# wirelessrgbled.net
KiCad netlist of a schematic drawn in EAGLE
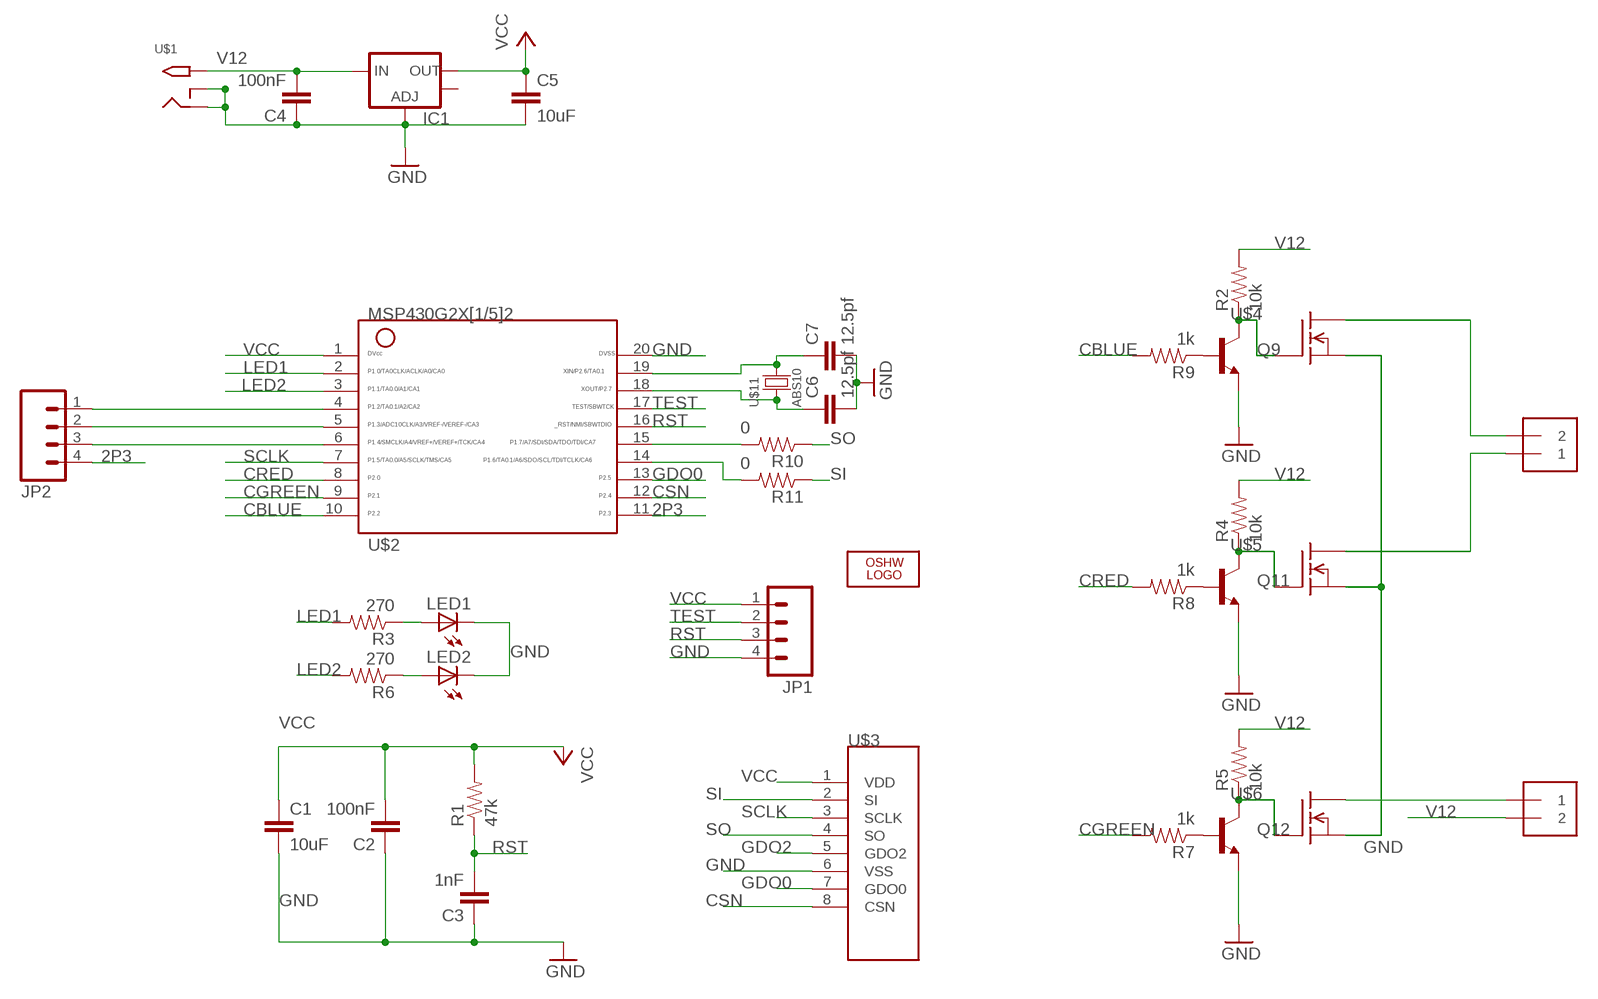
[diagram p0: schematic, sheet 1]

(export (version "E")
  (design (tool "Eeschema 10.0.6"))
  (components
    (comp (ref "C1")
      (value "10uF")
      (footprint "eagle-import:0805")
      (libsource (lib "eagle-import") (part "CAP0805"))
    )
    (comp (ref "C2")
      (value "100nF")
      (footprint "eagle-import:0805")
      (libsource (lib "eagle-import") (part "CAP0805"))
    )
    (comp (ref "C3")
      (value "1nF")
      (footprint "eagle-import:0805")
      (libsource (lib "eagle-import") (part "CAP0805"))
    )
    (comp (ref "C4")
      (value "100nF")
      (footprint "eagle-import:0805")
      (libsource (lib "eagle-import") (part "CAP0805"))
    )
    (comp (ref "C5")
      (value "10uF")
      (footprint "eagle-import:0805")
      (libsource (lib "eagle-import") (part "CAP0805"))
    )
    (comp (ref "C6")
      (value "12.5pf")
      (footprint "eagle-import:0805")
      (libsource (lib "eagle-import") (part "CAP0805"))
    )
    (comp (ref "C7")
      (value "12.5pf")
      (footprint "eagle-import:0805")
      (libsource (lib "eagle-import") (part "CAP0805"))
    )
    (comp (ref "IC1")
      (value "V_REG_LM1117SOT223")
      (footprint "eagle-import:SOT223")
      (libsource (lib "eagle-import") (part "V_REG_LM1117SOT223"))
    )
    (comp (ref "J1")
      (value "1X2-3.5MM")
      (footprint "eagle-import:1X2-3.5MM")
      (libsource (lib "eagle-import") (part "1X2-3.5MM"))
    )
    (comp (ref "J2")
      (value "1X2-3.5MM")
      (footprint "eagle-import:1X2-3.5MM")
      (libsource (lib "eagle-import") (part "1X2-3.5MM"))
    )
    (comp (ref "JP1")
      (value "M04PTH")
      (footprint "eagle-import:1X04")
      (libsource (lib "eagle-import") (part "M04PTH"))
    )
    (comp (ref "JP2")
      (value "M04PTH")
      (footprint "eagle-import:1X04")
      (libsource (lib "eagle-import") (part "M04PTH"))
    )
    (comp (ref "LED1")
      (value "LEDCHIPLED_0805")
      (footprint "eagle-import:CHIPLED_0805")
      (libsource (lib "eagle-import") (part "LEDCHIPLED_0805"))
    )
    (comp (ref "LED2")
      (value "LEDCHIPLED_0805")
      (footprint "eagle-import:CHIPLED_0805")
      (libsource (lib "eagle-import") (part "LEDCHIPLED_0805"))
    )
    (comp (ref "LOGO1")
      (value "OSHW_LOGO_10MILX0200-NT")
      (footprint "eagle-import:OSHW_10X200_NOTEXT")
      (libsource (lib "eagle-import") (part "OSHW_LOGO_10MILX0200-NT"))
    )
    (comp (ref "Q9")
      (value "TRANSISTOR_NPNSOT23")
      (footprint "eagle-import:SOT23")
      (libsource (lib "eagle-import") (part "TRANSISTOR_NPNSOT23"))
    )
    (comp (ref "Q11")
      (value "TRANSISTOR_NPNSOT23")
      (footprint "eagle-import:SOT23")
      (libsource (lib "eagle-import") (part "TRANSISTOR_NPNSOT23"))
    )
    (comp (ref "Q12")
      (value "TRANSISTOR_NPNSOT23")
      (footprint "eagle-import:SOT23")
      (libsource (lib "eagle-import") (part "TRANSISTOR_NPNSOT23"))
    )
    (comp (ref "R1")
      (value "47k")
      (footprint "eagle-import:0805")
      (libsource (lib "eagle-import") (part "RESISTOR0805-RES"))
    )
    (comp (ref "R2")
      (value "10k")
      (footprint "eagle-import:0805")
      (libsource (lib "eagle-import") (part "RESISTOR0805-RES"))
    )
    (comp (ref "R3")
      (value "270")
      (footprint "eagle-import:0805")
      (libsource (lib "eagle-import") (part "RESISTOR0805-RES"))
    )
    (comp (ref "R4")
      (value "10k")
      (footprint "eagle-import:0805")
      (libsource (lib "eagle-import") (part "RESISTOR0805-RES"))
    )
    (comp (ref "R5")
      (value "10k")
      (footprint "eagle-import:0805")
      (libsource (lib "eagle-import") (part "RESISTOR0805-RES"))
    )
    (comp (ref "R6")
      (value "270")
      (footprint "eagle-import:0805")
      (libsource (lib "eagle-import") (part "RESISTOR0805-RES"))
    )
    (comp (ref "R7")
      (value "1k")
      (footprint "eagle-import:0805")
      (libsource (lib "eagle-import") (part "RESISTOR0805-RES"))
    )
    (comp (ref "R8")
      (value "1k")
      (footprint "eagle-import:0805")
      (libsource (lib "eagle-import") (part "RESISTOR0805-RES"))
    )
    (comp (ref "R9")
      (value "1k")
      (footprint "eagle-import:0805")
      (libsource (lib "eagle-import") (part "RESISTOR0805-RES"))
    )
    (comp (ref "R10")
      (value "0")
      (footprint "eagle-import:0805")
      (libsource (lib "eagle-import") (part "RESISTOR0805-RES"))
    )
    (comp (ref "R11")
      (value "0")
      (footprint "eagle-import:0805")
      (libsource (lib "eagle-import") (part "RESISTOR0805-RES"))
    )
    (comp (ref "U$1")
      (value "2.1MMJACKTHM")
      (footprint "eagle-import:PJ-102A")
      (libsource (lib "eagle-import") (part "2.1MMJACKTHM"))
    )
    (comp (ref "U$2")
      (value "G2X[1/5]2---PW20")
      (footprint "eagle-import:PW20")
      (libsource (lib "eagle-import") (part "G2X[1/5]2---PW20"))
    )
    (comp (ref "U$3")
      (value "CC2500-MODULE")
      (footprint "eagle-import:CC2500-MODULE")
      (libsource (lib "eagle-import") (part "CC2500-MODULE"))
    )
    (comp (ref "U$4")
      (value "BUK92150")
      (footprint "eagle-import:TO252")
      (libsource (lib "eagle-import") (part "BUK92150"))
    )
    (comp (ref "U$5")
      (value "BUK92150")
      (footprint "eagle-import:TO252")
      (libsource (lib "eagle-import") (part "BUK92150"))
    )
    (comp (ref "U$6")
      (value "BUK92150")
      (footprint "eagle-import:TO252")
      (libsource (lib "eagle-import") (part "BUK92150"))
    )
    (comp (ref "U$11")
      (value "ABS10")
      (footprint "eagle-import:ABS10")
      (libsource (lib "eagle-import") (part "ABS10"))
    )
  )
  (nets
    (net (code "1") (name "/2P3") (class "Default")
      (node (ref "JP2") (pin "4") (pinfunction "4_4") (pintype "passive"))
      (node (ref "U$2") (pin "11") (pinfunction "11_11") (pintype "bidirectional"))
    )
    (net (code "2") (name "/CBLUE") (class "Default")
      (node (ref "R9") (pin "2") (pinfunction "2_2") (pintype "passive"))
      (node (ref "U$2") (pin "10") (pinfunction "10_10") (pintype "bidirectional"))
    )
    (net (code "3") (name "/CGREEN") (class "Default")
      (node (ref "R7") (pin "2") (pinfunction "2_2") (pintype "passive"))
      (node (ref "U$2") (pin "9") (pinfunction "9_9") (pintype "bidirectional"))
    )
    (net (code "4") (name "/CRED") (class "Default")
      (node (ref "R8") (pin "2") (pinfunction "2_2") (pintype "passive"))
      (node (ref "U$2") (pin "8") (pinfunction "8_8") (pintype "bidirectional"))
    )
    (net (code "5") (name "/CSN") (class "Default")
      (node (ref "U$2") (pin "12") (pinfunction "12_12") (pintype "bidirectional"))
      (node (ref "U$3") (pin "8") (pinfunction "CSN_8") (pintype "bidirectional"))
    )
    (net (code "6") (name "/GDO0") (class "Default")
      (node (ref "U$2") (pin "13") (pinfunction "13_13") (pintype "bidirectional"))
      (node (ref "U$3") (pin "7") (pinfunction "GDO0_7") (pintype "bidirectional"))
    )
    (net (code "7") (name "/GDO2") (class "Default")
      (node (ref "U$3") (pin "5") (pinfunction "GDO2_5") (pintype "bidirectional"))
    )
    (net (code "8") (name "/LED1") (class "Default")
      (node (ref "R3") (pin "2") (pinfunction "2_2") (pintype "passive"))
      (node (ref "U$2") (pin "2") (pinfunction "2_2") (pintype "bidirectional"))
    )
    (net (code "9") (name "/LED2") (class "Default")
      (node (ref "R6") (pin "2") (pinfunction "2_2") (pintype "passive"))
      (node (ref "U$2") (pin "3") (pinfunction "3_3") (pintype "bidirectional"))
    )
    (net (code "10") (name "/RST") (class "Default")
      (node (ref "C3") (pin "2") (pinfunction "2_2") (pintype "passive"))
      (node (ref "JP1") (pin "3") (pinfunction "3_3") (pintype "passive"))
      (node (ref "R1") (pin "1") (pinfunction "1_1") (pintype "passive"))
      (node (ref "U$2") (pin "16") (pinfunction "16_16") (pintype "bidirectional"))
    )
    (net (code "11") (name "/SCLK") (class "Default")
      (node (ref "U$2") (pin "7") (pinfunction "7_7") (pintype "bidirectional"))
      (node (ref "U$3") (pin "3") (pinfunction "SCLK_3") (pintype "bidirectional"))
    )
    (net (code "12") (name "/SI") (class "Default")
      (node (ref "R11") (pin "1") (pinfunction "1_1") (pintype "passive"))
      (node (ref "U$3") (pin "2") (pinfunction "SI_2") (pintype "bidirectional"))
    )
    (net (code "13") (name "/SO") (class "Default")
      (node (ref "R10") (pin "1") (pinfunction "1_1") (pintype "passive"))
      (node (ref "U$3") (pin "4") (pinfunction "SO_4") (pintype "bidirectional"))
    )
    (net (code "14") (name "/TEST") (class "Default")
      (node (ref "JP1") (pin "2") (pinfunction "2_2") (pintype "passive"))
      (node (ref "U$2") (pin "17") (pinfunction "17_17") (pintype "bidirectional"))
    )
    (net (code "15") (name "/V12") (class "Default")
      (node (ref "C4") (pin "2") (pinfunction "2_2") (pintype "passive"))
      (node (ref "IC1") (pin "3") (pinfunction "IN_3") (pintype "input"))
      (node (ref "J2") (pin "2") (pinfunction "2_2") (pintype "passive"))
      (node (ref "R2") (pin "2") (pinfunction "2_2") (pintype "passive"))
      (node (ref "R4") (pin "2") (pinfunction "2_2") (pintype "passive"))
      (node (ref "R5") (pin "2") (pinfunction "2_2") (pintype "passive"))
      (node (ref "U$1") (pin "TIP") (pinfunction "TIP_TIP") (pintype "bidirectional"))
    )
    (net (code "16") (name "GND") (class "Default")
      (node (ref "C1") (pin "2") (pinfunction "2_2") (pintype "passive"))
      (node (ref "C2") (pin "1") (pinfunction "1_1") (pintype "passive"))
      (node (ref "C3") (pin "1") (pinfunction "1_1") (pintype "passive"))
      (node (ref "C4") (pin "1") (pinfunction "1_1") (pintype "passive"))
      (node (ref "C5") (pin "2") (pinfunction "2_2") (pintype "passive"))
      (node (ref "C6") (pin "2") (pinfunction "2_2") (pintype "passive"))
      (node (ref "C7") (pin "2") (pinfunction "2_2") (pintype "passive"))
      (node (ref "IC1") (pin "1") (pinfunction "ADJ_1") (pintype "input"))
      (node (ref "JP1") (pin "4") (pinfunction "4_4") (pintype "passive"))
      (node (ref "LED1") (pin "C") (pinfunction "C_C") (pintype "passive"))
      (node (ref "LED2") (pin "C") (pinfunction "C_C") (pintype "passive"))
      (node (ref "Q11") (pin "2") (pinfunction "E_2") (pintype "passive"))
      (node (ref "Q12") (pin "2") (pinfunction "E_2") (pintype "passive"))
      (node (ref "Q9") (pin "2") (pinfunction "E_2") (pintype "passive"))
      (node (ref "U$1") (pin "RING") (pinfunction "RING_RING") (pintype "bidirectional"))
      (node (ref "U$1") (pin "RING_SW") (pinfunction "RING_SW_RING_SW") (pintype "bidirectional"))
      (node (ref "U$2") (pin "20") (pinfunction "20_20") (pintype "bidirectional"))
      (node (ref "U$3") (pin "6") (pinfunction "VSS_6") (pintype "bidirectional"))
      (node (ref "U$4") (pin "3") (pinfunction "S_3") (pintype "passive"))
      (node (ref "U$5") (pin "3") (pinfunction "S_3") (pintype "passive"))
      (node (ref "U$6") (pin "3") (pinfunction "S_3") (pintype "passive"))
    )
    (net (code "17") (name "Net-(C6-Pad1)") (class "Default")
      (node (ref "C6") (pin "1") (pinfunction "1_1") (pintype "passive"))
      (node (ref "U$11") (pin "P$1") (pinfunction "P$1_P$1") (pintype "passive"))
      (node (ref "U$2") (pin "18") (pinfunction "18_18") (pintype "bidirectional"))
    )
    (net (code "18") (name "Net-(C7-Pad1)") (class "Default")
      (node (ref "C7") (pin "1") (pinfunction "1_1") (pintype "passive"))
      (node (ref "U$11") (pin "P$2") (pinfunction "P$2_P$2") (pintype "passive"))
      (node (ref "U$2") (pin "19") (pinfunction "19_19") (pintype "bidirectional"))
    )
    (net (code "19") (name "Net-(JP2-Pad1)") (class "Default")
      (node (ref "JP2") (pin "1") (pinfunction "1_1") (pintype "passive"))
      (node (ref "U$2") (pin "4") (pinfunction "4_4") (pintype "bidirectional"))
    )
    (net (code "20") (name "Net-(JP2-Pad2)") (class "Default")
      (node (ref "JP2") (pin "2") (pinfunction "2_2") (pintype "passive"))
      (node (ref "U$2") (pin "5") (pinfunction "5_5") (pintype "bidirectional"))
    )
    (net (code "21") (name "Net-(JP2-Pad3)") (class "Default")
      (node (ref "JP2") (pin "3") (pinfunction "3_3") (pintype "passive"))
      (node (ref "U$2") (pin "6") (pinfunction "6_6") (pintype "bidirectional"))
    )
    (net (code "22") (name "Net-(LED1-PadA)") (class "Default")
      (node (ref "LED1") (pin "A") (pinfunction "A_A") (pintype "passive"))
      (node (ref "R3") (pin "1") (pinfunction "1_1") (pintype "passive"))
    )
    (net (code "23") (name "Net-(LED2-PadA)") (class "Default")
      (node (ref "LED2") (pin "A") (pinfunction "A_A") (pintype "passive"))
      (node (ref "R6") (pin "1") (pinfunction "1_1") (pintype "passive"))
    )
    (net (code "24") (name "Net-(Q9-B)") (class "Default")
      (node (ref "Q9") (pin "1") (pinfunction "B_1") (pintype "passive"))
      (node (ref "R9") (pin "1") (pinfunction "1_1") (pintype "passive"))
    )
    (net (code "25") (name "Net-(Q9-C)") (class "Default")
      (node (ref "Q9") (pin "3") (pinfunction "C_3") (pintype "passive"))
      (node (ref "R2") (pin "1") (pinfunction "1_1") (pintype "passive"))
      (node (ref "U$4") (pin "1") (pinfunction "G_1") (pintype "passive"))
    )
    (net (code "26") (name "Net-(Q11-B)") (class "Default")
      (node (ref "Q11") (pin "1") (pinfunction "B_1") (pintype "passive"))
      (node (ref "R8") (pin "1") (pinfunction "1_1") (pintype "passive"))
    )
    (net (code "27") (name "Net-(Q11-C)") (class "Default")
      (node (ref "Q11") (pin "3") (pinfunction "C_3") (pintype "passive"))
      (node (ref "R4") (pin "1") (pinfunction "1_1") (pintype "passive"))
      (node (ref "U$5") (pin "1") (pinfunction "G_1") (pintype "passive"))
    )
    (net (code "28") (name "Net-(Q12-B)") (class "Default")
      (node (ref "Q12") (pin "1") (pinfunction "B_1") (pintype "passive"))
      (node (ref "R7") (pin "1") (pinfunction "1_1") (pintype "passive"))
    )
    (net (code "29") (name "Net-(Q12-C)") (class "Default")
      (node (ref "Q12") (pin "3") (pinfunction "C_3") (pintype "passive"))
      (node (ref "R5") (pin "1") (pinfunction "1_1") (pintype "passive"))
      (node (ref "U$6") (pin "1") (pinfunction "G_1") (pintype "passive"))
    )
    (net (code "30") (name "Net-(R10-Pad2)") (class "Default")
      (node (ref "R10") (pin "2") (pinfunction "2_2") (pintype "passive"))
      (node (ref "U$2") (pin "15") (pinfunction "15_15") (pintype "bidirectional"))
    )
    (net (code "31") (name "Net-(R11-Pad2)") (class "Default")
      (node (ref "R11") (pin "2") (pinfunction "2_2") (pintype "passive"))
      (node (ref "U$2") (pin "14") (pinfunction "14_14") (pintype "bidirectional"))
    )
    (net (code "32") (name "Net-(U$4-D)") (class "Default")
      (node (ref "J1") (pin "2") (pinfunction "2_2") (pintype "passive"))
      (node (ref "U$4") (pin "2") (pinfunction "D_2") (pintype "passive"))
    )
    (net (code "33") (name "Net-(U$5-D)") (class "Default")
      (node (ref "J1") (pin "1") (pinfunction "1_1") (pintype "passive"))
      (node (ref "U$5") (pin "2") (pinfunction "D_2") (pintype "passive"))
    )
    (net (code "34") (name "Net-(U$6-D)") (class "Default")
      (node (ref "J2") (pin "1") (pinfunction "1_1") (pintype "passive"))
      (node (ref "U$6") (pin "2") (pinfunction "D_2") (pintype "passive"))
    )
    (net (code "35") (name "VCC") (class "Default")
      (node (ref "C1") (pin "1") (pinfunction "1_1") (pintype "passive"))
      (node (ref "C2") (pin "2") (pinfunction "2_2") (pintype "passive"))
      (node (ref "C5") (pin "1") (pinfunction "1_1") (pintype "passive"))
      (node (ref "IC1") (pin "2") (pinfunction "OUT_2") (pintype "output"))
      (node (ref "JP1") (pin "1") (pinfunction "1_1") (pintype "passive"))
      (node (ref "R1") (pin "2") (pinfunction "2_2") (pintype "passive"))
      (node (ref "U$2") (pin "1") (pinfunction "1_1") (pintype "bidirectional"))
      (node (ref "U$3") (pin "1") (pinfunction "VDD_1") (pintype "bidirectional"))
    )
    (net (code "36") (name "unconnected-(IC1-OUT-Pad4)") (class "Default")
      (node (ref "IC1") (pin "4") (pinfunction "OUT_4") (pintype "output"))
    )
  )
)
